# simple-loop-active5.net
KiCad netlist of a schematic drawn in EAGLE
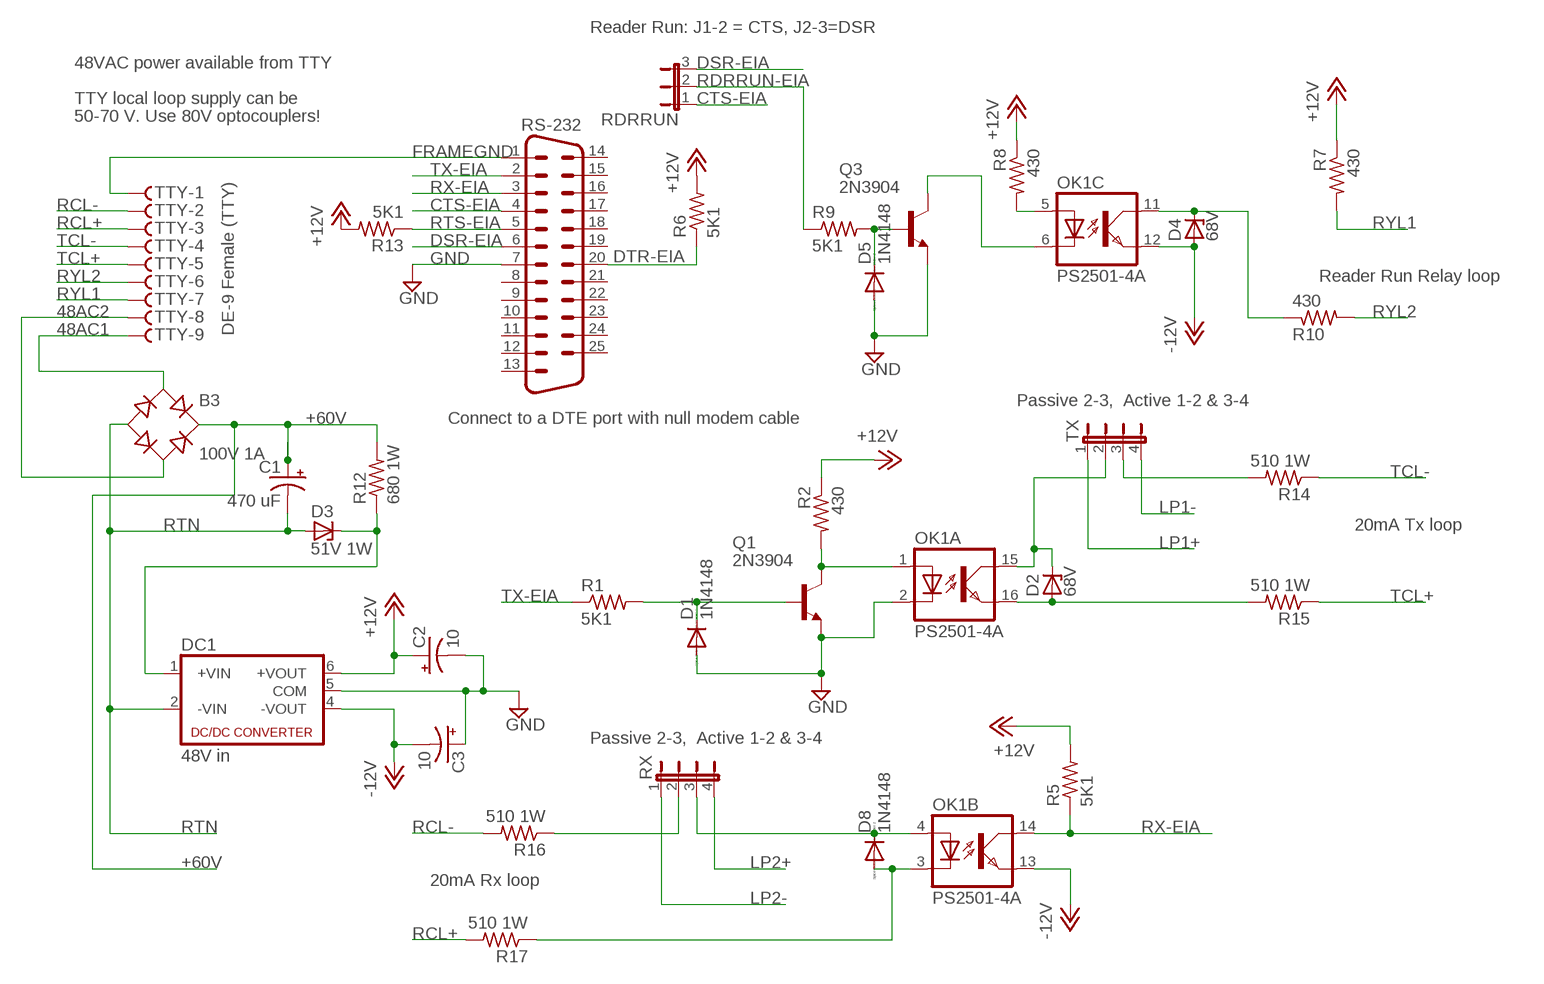
[diagram p0: schematic, sheet 1]
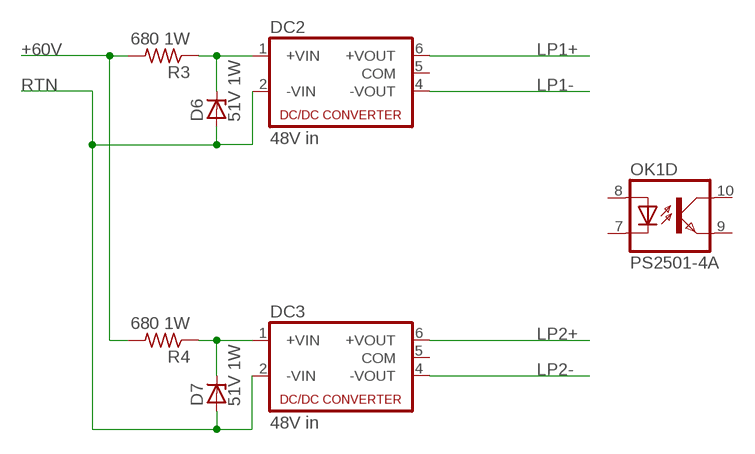
[diagram p1: schematic, sheet 2]

(export (version "E")
  (design (tool "Eeschema 10.0.6"))
  (components
    (comp (ref "B3")
      (value "100V 1A")
      (footprint "eagle-import:RB1A")
      (libsource (lib "eagle-import") (part "RB1A"))
    )
    (comp (ref "C1")
      (value "470 uF")
      (footprint "eagle-import:E7,5-18")
      (libsource (lib "eagle-import") (part "CPOL-USE7.5-18"))
    )
    (comp (ref "C2")
      (value "10")
      (footprint "eagle-import:B45181A")
      (libsource (lib "eagle-import") (part "CPOL-USB45181A"))
    )
    (comp (ref "C3")
      (value "10")
      (footprint "eagle-import:B45181A")
      (libsource (lib "eagle-import") (part "CPOL-USB45181A"))
    )
    (comp (ref "D1")
      (value "1N4148")
      (footprint "eagle-import:DO35-10")
      (libsource (lib "eagle-import") (part "1N4148DO35-10"))
    )
    (comp (ref "D2")
      (value "68V")
      (footprint "eagle-import:DO41Z10")
      (libsource (lib "eagle-import") (part "ZENER-DIODEDO41Z10"))
    )
    (comp (ref "D3")
      (value "51V 1W")
      (footprint "eagle-import:DO41Z10")
      (libsource (lib "eagle-import") (part "ZENER-DIODEDO41Z10"))
    )
    (comp (ref "D4")
      (value "68V")
      (footprint "eagle-import:DO41Z10")
      (libsource (lib "eagle-import") (part "ZENER-DIODEDO41Z10"))
    )
    (comp (ref "D5")
      (value "1N4148")
      (footprint "eagle-import:DO35-10")
      (libsource (lib "eagle-import") (part "1N4148DO35-10"))
    )
    (comp (ref "D8")
      (value "1N4148")
      (footprint "eagle-import:DO35-10")
      (libsource (lib "eagle-import") (part "1N4148DO35-10"))
    )
    (comp (ref "DC1")
      (value "48V in")
      (footprint "eagle-import:NMA")
      (fields (field (name "MF") "C & D TECHNOLOGIES, INC") (field (name "MPN") "NMA0515SC"))
      (libsource (lib "eagle-import") (part "NMA"))
    )
    (comp (ref "OK1")
      (value "PS2501-4A")
      (footprint "eagle-import:DIL16")
      (fields (field (name "MF") "VISHAY/TELEFUNKEN") (field (name "MPN") "ILQ1"))
      (libsource (lib "eagle-import") (part "ILQ1"))
    )
    (comp (ref "Q1")
      (value "2N3904")
      (footprint "eagle-import:TO92")
      (libsource (lib "eagle-import") (part "2N3904"))
    )
    (comp (ref "Q3")
      (value "2N3904")
      (footprint "eagle-import:TO92")
      (libsource (lib "eagle-import") (part "2N3904"))
    )
    (comp (ref "R1")
      (value "5K1")
      (footprint "eagle-import:0207_10")
      (libsource (lib "eagle-import") (part "R-US_0207/10"))
    )
    (comp (ref "R2")
      (value "430")
      (footprint "eagle-import:0207_10")
      (libsource (lib "eagle-import") (part "R-US_0207/10"))
    )
    (comp (ref "R5")
      (value "5K1")
      (footprint "eagle-import:0207_10")
      (libsource (lib "eagle-import") (part "R-US_0207/10"))
    )
    (comp (ref "R6")
      (value "5K1")
      (footprint "eagle-import:0207_10")
      (libsource (lib "eagle-import") (part "R-US_0207/10"))
    )
    (comp (ref "R7")
      (value "430")
      (footprint "eagle-import:0207_10")
      (libsource (lib "eagle-import") (part "R-US_0207/10"))
    )
    (comp (ref "R8")
      (value "430")
      (footprint "eagle-import:0207_10")
      (libsource (lib "eagle-import") (part "R-US_0207/10"))
    )
    (comp (ref "R9")
      (value "5K1")
      (footprint "eagle-import:0207_10")
      (libsource (lib "eagle-import") (part "R-US_0207/10"))
    )
    (comp (ref "R10")
      (value "430")
      (footprint "eagle-import:0207_10")
      (libsource (lib "eagle-import") (part "R-US_0207/10"))
    )
    (comp (ref "R12")
      (value "680 1W")
      (footprint "eagle-import:P0817V")
      (libsource (lib "eagle-import") (part "R-US_0817/7V"))
    )
    (comp (ref "R13")
      (value "5K1")
      (footprint "eagle-import:0207_10")
      (libsource (lib "eagle-import") (part "R-US_0207/10"))
    )
    (comp (ref "R14")
      (value "510 1W")
      (footprint "eagle-import:P0817V")
      (libsource (lib "eagle-import") (part "R-US_0817/7V"))
    )
    (comp (ref "R15")
      (value "510 1W")
      (footprint "eagle-import:P0817V")
      (libsource (lib "eagle-import") (part "R-US_0817/7V"))
    )
    (comp (ref "R16")
      (value "510 1W")
      (footprint "eagle-import:P0817V")
      (libsource (lib "eagle-import") (part "R-US_0817/7V"))
    )
    (comp (ref "R17")
      (value "510 1W")
      (footprint "eagle-import:P0817V")
      (libsource (lib "eagle-import") (part "R-US_0817/7V"))
    )
    (comp (ref "RDRRUN")
      (value "JP2E")
      (footprint "eagle-import:JP2")
      (libsource (lib "eagle-import") (part "JP2E"))
    )
    (comp (ref "RS-232")
      (value "M25H")
      (footprint "eagle-import:M25H")
      (libsource (lib "eagle-import") (part "M25H"))
    )
    (comp (ref "RX")
      (value "JP4E")
      (footprint "eagle-import:JP4")
      (libsource (lib "eagle-import") (part "JP4E"))
    )
    (comp (ref "TTY")
      (value "F09HS")
      (footprint "eagle-import:F09H")
      (libsource (lib "eagle-import") (part "F09?SH"))
    )
    (comp (ref "TX")
      (value "JP4E")
      (footprint "eagle-import:JP4")
      (libsource (lib "eagle-import") (part "JP4E"))
    )
    (comp (ref "D6")
      (value "51V 1W")
      (footprint "eagle-import:DO41Z10")
      (libsource (lib "eagle-import") (part "ZENER-DIODEDO41Z10"))
    )
    (comp (ref "D7")
      (value "51V 1W")
      (footprint "eagle-import:DO41Z10")
      (libsource (lib "eagle-import") (part "ZENER-DIODEDO41Z10"))
    )
    (comp (ref "DC2")
      (value "48V in")
      (footprint "eagle-import:NMA")
      (fields (field (name "MF") "C & D TECHNOLOGIES, INC") (field (name "MPN") "NMA0515SC"))
      (libsource (lib "eagle-import") (part "NMA"))
    )
    (comp (ref "DC3")
      (value "48V in")
      (footprint "eagle-import:NMA")
      (fields (field (name "MF") "C & D TECHNOLOGIES, INC") (field (name "MPN") "NMA0515SC"))
      (libsource (lib "eagle-import") (part "NMA"))
    )
    (comp (ref "R3")
      (value "680 1W")
      (footprint "eagle-import:P0817V")
      (libsource (lib "eagle-import") (part "R-US_0817/7V"))
    )
    (comp (ref "R4")
      (value "680 1W")
      (footprint "eagle-import:P0817V")
      (libsource (lib "eagle-import") (part "R-US_0817/7V"))
    )
  )
  (nets
    (net (code "1") (name "+12V") (class "Default")
      (node (ref "C2") (pin "+") (pinfunction "+_+") (pintype "passive"))
      (node (ref "DC1") (pin "6") (pinfunction "+VOUT_6") (pintype "passive"))
      (node (ref "R13") (pin "2") (pinfunction "2_2") (pintype "passive"))
      (node (ref "R2") (pin "1") (pinfunction "1_1") (pintype "passive"))
      (node (ref "R5") (pin "2") (pinfunction "2_2") (pintype "passive"))
      (node (ref "R6") (pin "2") (pinfunction "2_2") (pintype "passive"))
      (node (ref "R7") (pin "1") (pinfunction "1_1") (pintype "passive"))
      (node (ref "R8") (pin "1") (pinfunction "1_1") (pintype "passive"))
    )
    (net (code "2") (name "+60V") (class "Default")
      (node (ref "B3") (pin "+") (pinfunction "+_+") (pintype "passive"))
      (node (ref "C1") (pin "+") (pinfunction "+_+") (pintype "passive"))
      (node (ref "R12") (pin "2") (pinfunction "2_2") (pintype "passive"))
      (node (ref "R3") (pin "2") (pinfunction "2_2") (pintype "passive"))
      (node (ref "R4") (pin "2") (pinfunction "2_2") (pintype "passive"))
    )
    (net (code "3") (name "-12V") (class "Default")
      (node (ref "C3") (pin "-") (pinfunction "-_-") (pintype "passive"))
      (node (ref "D4") (pin "A") (pinfunction "A_A") (pintype "passive"))
      (node (ref "DC1") (pin "4") (pinfunction "-VOUT_4") (pintype "passive"))
      (node (ref "OK1") (pin "12") (pinfunction "EMIT_12") (pintype "passive"))
      (node (ref "OK1") (pin "13") (pinfunction "EMIT_13") (pintype "passive"))
    )
    (net (code "4") (name "48AC1") (class "Default")
      (node (ref "B3") (pin "AC1") (pinfunction "AC1_AC1") (pintype "passive"))
      (node (ref "TTY") (pin "9") (pinfunction "F_9") (pintype "passive"))
    )
    (net (code "5") (name "48AC2") (class "Default")
      (node (ref "B3") (pin "AC2") (pinfunction "AC2_AC2") (pintype "passive"))
      (node (ref "TTY") (pin "8") (pinfunction "F_8") (pintype "passive"))
    )
    (net (code "6") (name "CTS-EIA") (class "Default")
      (node (ref "RDRRUN") (pin "1") (pinfunction "1_1") (pintype "passive"))
      (node (ref "RS-232") (pin "4") (pinfunction "4_4") (pintype "passive"))
    )
    (net (code "7") (name "DSR-EIA") (class "Default")
      (node (ref "RDRRUN") (pin "3") (pinfunction "3_3") (pintype "passive"))
      (node (ref "RS-232") (pin "6") (pinfunction "6_6") (pintype "passive"))
    )
    (net (code "8") (name "DTR-EIA") (class "Default")
      (node (ref "R6") (pin "1") (pinfunction "1_1") (pintype "passive"))
      (node (ref "RS-232") (pin "20") (pinfunction "20_20") (pintype "passive"))
    )
    (net (code "9") (name "FRAMEGND") (class "Default")
      (node (ref "RS-232") (pin "1") (pinfunction "1_1") (pintype "passive"))
      (node (ref "TTY") (pin "1") (pinfunction "F_1") (pintype "passive"))
    )
    (net (code "10") (name "GND") (class "Default")
      (node (ref "C2") (pin "-") (pinfunction "-_-") (pintype "passive"))
      (node (ref "C3") (pin "+") (pinfunction "+_+") (pintype "passive"))
      (node (ref "D1") (pin "A") (pinfunction "A_A") (pintype "passive"))
      (node (ref "D5") (pin "A") (pinfunction "A_A") (pintype "passive"))
      (node (ref "DC1") (pin "5") (pinfunction "COM_5") (pintype "passive"))
      (node (ref "OK1") (pin "2") (pinfunction "C_2") (pintype "passive"))
      (node (ref "Q1") (pin "3") (pinfunction "E_3") (pintype "passive"))
      (node (ref "Q3") (pin "3") (pinfunction "E_3") (pintype "passive"))
      (node (ref "RS-232") (pin "7") (pinfunction "7_7") (pintype "passive"))
    )
    (net (code "11") (name "LP1+") (class "Default")
      (node (ref "DC2") (pin "6") (pinfunction "+VOUT_6") (pintype "passive"))
      (node (ref "TX") (pin "1") (pinfunction "1_1") (pintype "passive"))
    )
    (net (code "12") (name "LP1-") (class "Default")
      (node (ref "DC2") (pin "4") (pinfunction "-VOUT_4") (pintype "passive"))
      (node (ref "TX") (pin "4") (pinfunction "4_4") (pintype "passive"))
    )
    (net (code "13") (name "LP2+") (class "Default")
      (node (ref "DC3") (pin "6") (pinfunction "+VOUT_6") (pintype "passive"))
      (node (ref "RX") (pin "4") (pinfunction "4_4") (pintype "passive"))
    )
    (net (code "14") (name "LP2-") (class "Default")
      (node (ref "DC3") (pin "4") (pinfunction "-VOUT_4") (pintype "passive"))
      (node (ref "RX") (pin "1") (pinfunction "1_1") (pintype "passive"))
    )
    (net (code "15") (name "Net-(DC1-+VIN)") (class "Default")
      (node (ref "D3") (pin "C") (pinfunction "C_C") (pintype "passive"))
      (node (ref "DC1") (pin "1") (pinfunction "+VIN_1") (pintype "passive"))
      (node (ref "R12") (pin "1") (pinfunction "1_1") (pintype "passive"))
    )
    (net (code "16") (name "Net-(DC2-+VIN)") (class "Default")
      (node (ref "D6") (pin "C") (pinfunction "C_C") (pintype "passive"))
      (node (ref "DC2") (pin "1") (pinfunction "+VIN_1") (pintype "passive"))
      (node (ref "R3") (pin "1") (pinfunction "1_1") (pintype "passive"))
    )
    (net (code "17") (name "Net-(DC3-+VIN)") (class "Default")
      (node (ref "D7") (pin "C") (pinfunction "C_C") (pintype "passive"))
      (node (ref "DC3") (pin "1") (pinfunction "+VIN_1") (pintype "passive"))
      (node (ref "R4") (pin "1") (pinfunction "1_1") (pintype "passive"))
    )
    (net (code "18") (name "Net-(OK1A-A)") (class "Default")
      (node (ref "OK1") (pin "1") (pinfunction "A_1") (pintype "passive"))
      (node (ref "Q1") (pin "1") (pinfunction "C_1") (pintype "passive"))
      (node (ref "R2") (pin "2") (pinfunction "2_2") (pintype "passive"))
    )
    (net (code "19") (name "Net-(OK1A-COL)") (class "Default")
      (node (ref "D2") (pin "C") (pinfunction "C_C") (pintype "passive"))
      (node (ref "OK1") (pin "15") (pinfunction "COL_15") (pintype "passive"))
      (node (ref "TX") (pin "2") (pinfunction "2_2") (pintype "passive"))
    )
    (net (code "20") (name "Net-(OK1A-EMIT)") (class "Default")
      (node (ref "D2") (pin "A") (pinfunction "A_A") (pintype "passive"))
      (node (ref "OK1") (pin "16") (pinfunction "EMIT_16") (pintype "passive"))
      (node (ref "R15") (pin "2") (pinfunction "2_2") (pintype "passive"))
    )
    (net (code "21") (name "Net-(OK1B-A)") (class "Default")
      (node (ref "D8") (pin "C") (pinfunction "C_C") (pintype "passive"))
      (node (ref "OK1") (pin "4") (pinfunction "A_4") (pintype "passive"))
      (node (ref "RX") (pin "3") (pinfunction "3_3") (pintype "passive"))
    )
    (net (code "22") (name "Net-(OK1B-C)") (class "Default")
      (node (ref "D8") (pin "A") (pinfunction "A_A") (pintype "passive"))
      (node (ref "OK1") (pin "3") (pinfunction "C_3") (pintype "passive"))
      (node (ref "R17") (pin "1") (pinfunction "1_1") (pintype "passive"))
    )
    (net (code "23") (name "Net-(OK1C-A)") (class "Default")
      (node (ref "OK1") (pin "5") (pinfunction "A_5") (pintype "passive"))
      (node (ref "R8") (pin "2") (pinfunction "2_2") (pintype "passive"))
    )
    (net (code "24") (name "Net-(OK1C-C)") (class "Default")
      (node (ref "OK1") (pin "6") (pinfunction "C_6") (pintype "passive"))
      (node (ref "Q3") (pin "1") (pinfunction "C_1") (pintype "passive"))
    )
    (net (code "25") (name "Net-(OK1C-COL)") (class "Default")
      (node (ref "D4") (pin "C") (pinfunction "C_C") (pintype "passive"))
      (node (ref "OK1") (pin "11") (pinfunction "COL_11") (pintype "passive"))
      (node (ref "R10") (pin "1") (pinfunction "1_1") (pintype "passive"))
    )
    (net (code "26") (name "Net-(Q1-B)") (class "Default")
      (node (ref "D1") (pin "C") (pinfunction "C_C") (pintype "passive"))
      (node (ref "Q1") (pin "2") (pinfunction "B_2") (pintype "passive"))
      (node (ref "R1") (pin "2") (pinfunction "2_2") (pintype "passive"))
    )
    (net (code "27") (name "Net-(Q3-B)") (class "Default")
      (node (ref "D5") (pin "C") (pinfunction "C_C") (pintype "passive"))
      (node (ref "Q3") (pin "2") (pinfunction "B_2") (pintype "passive"))
      (node (ref "R9") (pin "2") (pinfunction "2_2") (pintype "passive"))
    )
    (net (code "28") (name "Net-(R14-Pad2)") (class "Default")
      (node (ref "R14") (pin "2") (pinfunction "2_2") (pintype "passive"))
      (node (ref "TX") (pin "3") (pinfunction "3_3") (pintype "passive"))
    )
    (net (code "29") (name "Net-(R16-Pad1)") (class "Default")
      (node (ref "R16") (pin "1") (pinfunction "1_1") (pintype "passive"))
      (node (ref "RX") (pin "2") (pinfunction "2_2") (pintype "passive"))
    )
    (net (code "30") (name "RCL+") (class "Default")
      (node (ref "R17") (pin "2") (pinfunction "2_2") (pintype "passive"))
      (node (ref "TTY") (pin "3") (pinfunction "F_3") (pintype "passive"))
    )
    (net (code "31") (name "RCL-") (class "Default")
      (node (ref "R16") (pin "2") (pinfunction "2_2") (pintype "passive"))
      (node (ref "TTY") (pin "2") (pinfunction "F_2") (pintype "passive"))
    )
    (net (code "32") (name "RDRRUN-EIA") (class "Default")
      (node (ref "R9") (pin "1") (pinfunction "1_1") (pintype "passive"))
      (node (ref "RDRRUN") (pin "2") (pinfunction "2_2") (pintype "passive"))
    )
    (net (code "33") (name "RTN") (class "Default")
      (node (ref "B3") (pin "-") (pinfunction "-_-") (pintype "passive"))
      (node (ref "C1") (pin "-") (pinfunction "-_-") (pintype "passive"))
      (node (ref "D3") (pin "A") (pinfunction "A_A") (pintype "passive"))
      (node (ref "D6") (pin "A") (pinfunction "A_A") (pintype "passive"))
      (node (ref "D7") (pin "A") (pinfunction "A_A") (pintype "passive"))
      (node (ref "DC1") (pin "2") (pinfunction "-VIN_2") (pintype "passive"))
      (node (ref "DC2") (pin "2") (pinfunction "-VIN_2") (pintype "passive"))
      (node (ref "DC3") (pin "2") (pinfunction "-VIN_2") (pintype "passive"))
    )
    (net (code "34") (name "RTS-EIA") (class "Default")
      (node (ref "R13") (pin "1") (pinfunction "1_1") (pintype "passive"))
      (node (ref "RS-232") (pin "5") (pinfunction "5_5") (pintype "passive"))
    )
    (net (code "35") (name "RX-EIA") (class "Default")
      (node (ref "OK1") (pin "14") (pinfunction "COL_14") (pintype "passive"))
      (node (ref "R5") (pin "1") (pinfunction "1_1") (pintype "passive"))
      (node (ref "RS-232") (pin "3") (pinfunction "3_3") (pintype "passive"))
    )
    (net (code "36") (name "RYL1") (class "Default")
      (node (ref "R7") (pin "2") (pinfunction "2_2") (pintype "passive"))
      (node (ref "TTY") (pin "7") (pinfunction "F_7") (pintype "passive"))
    )
    (net (code "37") (name "RYL2") (class "Default")
      (node (ref "R10") (pin "2") (pinfunction "2_2") (pintype "passive"))
      (node (ref "TTY") (pin "6") (pinfunction "F_6") (pintype "passive"))
    )
    (net (code "38") (name "TCL+") (class "Default")
      (node (ref "R15") (pin "1") (pinfunction "1_1") (pintype "passive"))
      (node (ref "TTY") (pin "5") (pinfunction "F_5") (pintype "passive"))
    )
    (net (code "39") (name "TCL-") (class "Default")
      (node (ref "R14") (pin "1") (pinfunction "1_1") (pintype "passive"))
      (node (ref "TTY") (pin "4") (pinfunction "F_4") (pintype "passive"))
    )
    (net (code "40") (name "TX-EIA") (class "Default")
      (node (ref "R1") (pin "1") (pinfunction "1_1") (pintype "passive"))
      (node (ref "RS-232") (pin "2") (pinfunction "2_2") (pintype "passive"))
    )
    (net (code "41") (name "unconnected-(DC2-COM-Pad5)") (class "Default")
      (node (ref "DC2") (pin "5") (pinfunction "COM_5") (pintype "passive"))
    )
    (net (code "42") (name "unconnected-(DC3-COM-Pad5)") (class "Default")
      (node (ref "DC3") (pin "5") (pinfunction "COM_5") (pintype "passive"))
    )
    (net (code "43") (name "unconnected-(OK1D-A-Pad8)") (class "Default")
      (node (ref "OK1") (pin "8") (pinfunction "A_8") (pintype "passive"))
    )
    (net (code "44") (name "unconnected-(OK1D-C-Pad7)") (class "Default")
      (node (ref "OK1") (pin "7") (pinfunction "C_7") (pintype "passive"))
    )
    (net (code "45") (name "unconnected-(OK1D-COL-Pad10)") (class "Default")
      (node (ref "OK1") (pin "10") (pinfunction "COL_10") (pintype "passive"))
    )
    (net (code "46") (name "unconnected-(OK1D-EMIT-Pad9)") (class "Default")
      (node (ref "OK1") (pin "9") (pinfunction "EMIT_9") (pintype "passive"))
    )
    (net (code "47") (name "unconnected-(RS-232-Pad8)") (class "Default")
      (node (ref "RS-232") (pin "8") (pinfunction "8_8") (pintype "passive"))
    )
    (net (code "48") (name "unconnected-(RS-232-Pad9)") (class "Default")
      (node (ref "RS-232") (pin "9") (pinfunction "9_9") (pintype "passive"))
    )
    (net (code "49") (name "unconnected-(RS-232-Pad10)") (class "Default")
      (node (ref "RS-232") (pin "10") (pinfunction "10_10") (pintype "passive"))
    )
    (net (code "50") (name "unconnected-(RS-232-Pad11)") (class "Default")
      (node (ref "RS-232") (pin "11") (pinfunction "11_11") (pintype "passive"))
    )
    (net (code "51") (name "unconnected-(RS-232-Pad12)") (class "Default")
      (node (ref "RS-232") (pin "12") (pinfunction "12_12") (pintype "passive"))
    )
    (net (code "52") (name "unconnected-(RS-232-Pad13)") (class "Default")
      (node (ref "RS-232") (pin "13") (pinfunction "13_13") (pintype "passive"))
    )
    (net (code "53") (name "unconnected-(RS-232-Pad14)") (class "Default")
      (node (ref "RS-232") (pin "14") (pinfunction "14_14") (pintype "passive"))
    )
    (net (code "54") (name "unconnected-(RS-232-Pad15)") (class "Default")
      (node (ref "RS-232") (pin "15") (pinfunction "15_15") (pintype "passive"))
    )
    (net (code "55") (name "unconnected-(RS-232-Pad16)") (class "Default")
      (node (ref "RS-232") (pin "16") (pinfunction "16_16") (pintype "passive"))
    )
    (net (code "56") (name "unconnected-(RS-232-Pad17)") (class "Default")
      (node (ref "RS-232") (pin "17") (pinfunction "17_17") (pintype "passive"))
    )
    (net (code "57") (name "unconnected-(RS-232-Pad18)") (class "Default")
      (node (ref "RS-232") (pin "18") (pinfunction "18_18") (pintype "passive"))
    )
    (net (code "58") (name "unconnected-(RS-232-Pad19)") (class "Default")
      (node (ref "RS-232") (pin "19") (pinfunction "19_19") (pintype "passive"))
    )
    (net (code "59") (name "unconnected-(RS-232-Pad21)") (class "Default")
      (node (ref "RS-232") (pin "21") (pinfunction "21_21") (pintype "passive"))
    )
    (net (code "60") (name "unconnected-(RS-232-Pad22)") (class "Default")
      (node (ref "RS-232") (pin "22") (pinfunction "22_22") (pintype "passive"))
    )
    (net (code "61") (name "unconnected-(RS-232-Pad23)") (class "Default")
      (node (ref "RS-232") (pin "23") (pinfunction "23_23") (pintype "passive"))
    )
    (net (code "62") (name "unconnected-(RS-232-Pad24)") (class "Default")
      (node (ref "RS-232") (pin "24") (pinfunction "24_24") (pintype "passive"))
    )
    (net (code "63") (name "unconnected-(RS-232-Pad25)") (class "Default")
      (node (ref "RS-232") (pin "25") (pinfunction "25_25") (pintype "passive"))
    )
  )
)
